# nRF24-MultiPro.net
KiCad netlist of a schematic drawn in EAGLE
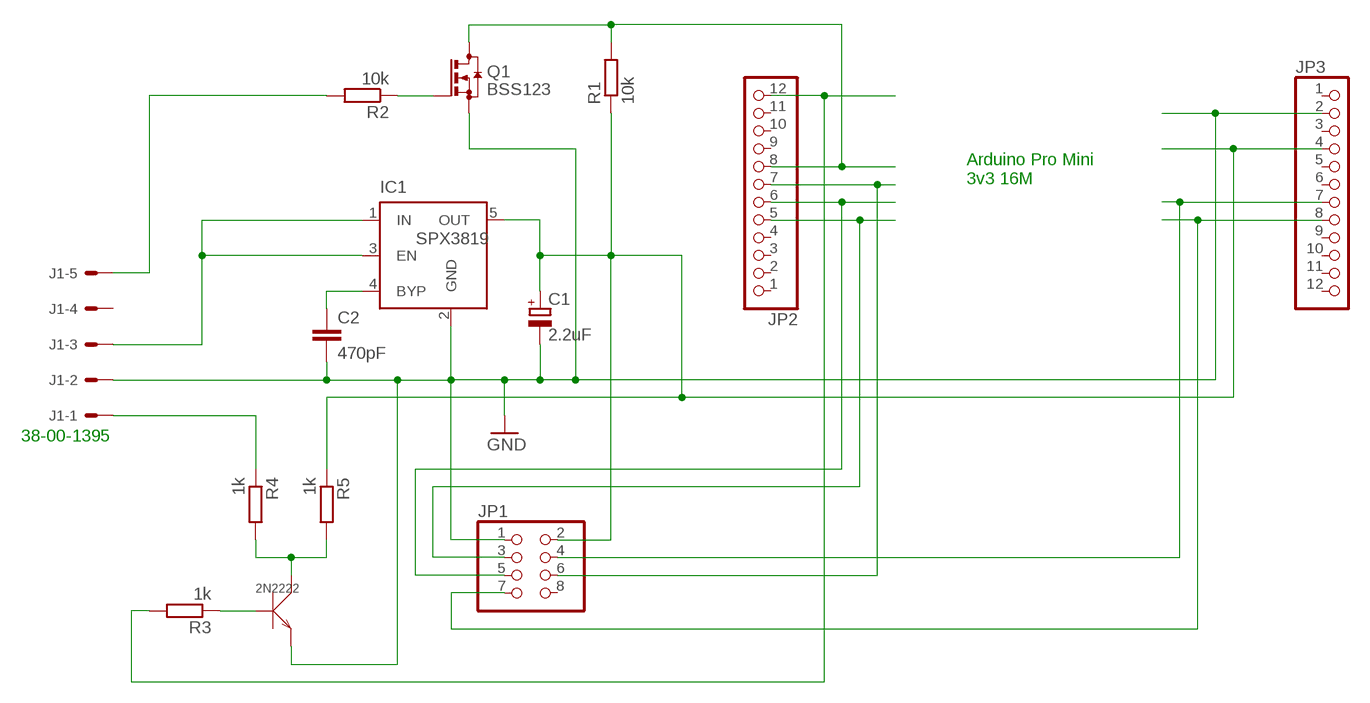
[diagram p0: schematic, sheet 1]

(export (version "E")
  (design (tool "Eeschema 10.0.6"))
  (components
    (comp (ref "2N2222")
      (value "TRANSISTOR-NPN")
      (footprint "eagle-import:SOT-23")
      (libsource (lib "eagle-import") (part "TRANSISTOR-NPN"))
    )
    (comp (ref "C1")
      (value "2.2uF")
      (footprint "eagle-import:A_3216-18W")
      (libsource (lib "eagle-import") (part "CPOL-EUA/3216-18W"))
    )
    (comp (ref "C2")
      (value "470pF")
      (footprint "eagle-import:C0805")
      (libsource (lib "eagle-import") (part "C-EUC0805"))
    )
    (comp (ref "IC1")
      (value "SPX3819")
      (footprint "eagle-import:SOT23-5")
      (libsource (lib "eagle-import") (part "MIC5219XX"))
    )
    (comp (ref "J1")
      (value "22-27-2051-05")
      (footprint "eagle-import:6410-05")
      (libsource (lib "eagle-import") (part "22-?-0527-2051"))
    )
    (comp (ref "JP1")
      (value "PINHD-2X4")
      (footprint "eagle-import:2X04")
      (libsource (lib "eagle-import") (part "PINHD-2X4"))
    )
    (comp (ref "JP2")
      (value "PINHD-1X12")
      (footprint "eagle-import:1X12")
      (libsource (lib "eagle-import") (part "PINHD-1X12"))
    )
    (comp (ref "JP3")
      (value "PINHD-1X12")
      (footprint "eagle-import:1X12")
      (libsource (lib "eagle-import") (part "PINHD-1X12"))
    )
    (comp (ref "Q1")
      (value "BSS123")
      (footprint "eagle-import:SOT23")
      (libsource (lib "eagle-import") (part "BSS123"))
    )
    (comp (ref "R1")
      (value "10k")
      (footprint "eagle-import:R0805")
      (libsource (lib "eagle-import") (part "R-EU_R0805"))
    )
    (comp (ref "R2")
      (value "10k")
      (footprint "eagle-import:R0805")
      (libsource (lib "eagle-import") (part "R-EU_R0805"))
    )
    (comp (ref "R3")
      (value "1k")
      (footprint "eagle-import:R0805")
      (libsource (lib "eagle-import") (part "R-EU_R0805"))
    )
    (comp (ref "R4")
      (value "1k")
      (footprint "eagle-import:R0805")
      (libsource (lib "eagle-import") (part "R-EU_R0805"))
    )
    (comp (ref "R5")
      (value "1k")
      (footprint "eagle-import:R0805")
      (libsource (lib "eagle-import") (part "R-EU_R0805"))
    )
  )
  (nets
    (net (code "1") (name "GND") (class "Default")
      (node (ref "2N2222") (pin "2") (pinfunction "E_2") (pintype "passive"))
      (node (ref "C1") (pin "-") (pinfunction "-_-") (pintype "passive"))
      (node (ref "C2") (pin "2") (pinfunction "2_2") (pintype "passive"))
      (node (ref "IC1") (pin "2") (pinfunction "GND_2") (pintype "power_in"))
      (node (ref "J1") (pin "2") (pinfunction "S_2") (pintype "passive"))
      (node (ref "JP1") (pin "1") (pinfunction "1_1") (pintype "passive"))
      (node (ref "JP3") (pin "2") (pinfunction "2_2") (pintype "passive"))
      (node (ref "Q1") (pin "2") (pinfunction "S_2") (pintype "passive"))
    )
    (net (code "2") (name "Net-(2N2222-B)") (class "Default")
      (node (ref "2N2222") (pin "1") (pinfunction "B_1") (pintype "passive"))
      (node (ref "R3") (pin "1") (pinfunction "1_1") (pintype "passive"))
    )
    (net (code "3") (name "Net-(2N2222-C)") (class "Default")
      (node (ref "2N2222") (pin "3") (pinfunction "C_3") (pintype "passive"))
      (node (ref "R4") (pin "2") (pinfunction "2_2") (pintype "passive"))
      (node (ref "R5") (pin "2") (pinfunction "2_2") (pintype "passive"))
    )
    (net (code "4") (name "Net-(IC1-BYP)") (class "Default")
      (node (ref "C2") (pin "1") (pinfunction "1_1") (pintype "passive"))
      (node (ref "IC1") (pin "4") (pinfunction "BYP_4") (pintype "passive"))
    )
    (net (code "5") (name "Net-(IC1-EN)") (class "Default")
      (node (ref "IC1") (pin "1") (pinfunction "IN_1") (pintype "input"))
      (node (ref "IC1") (pin "3") (pinfunction "EN_3") (pintype "input"))
      (node (ref "J1") (pin "3") (pinfunction "S_3") (pintype "passive"))
    )
    (net (code "6") (name "Net-(IC1-OUT)") (class "Default")
      (node (ref "C1") (pin "+") (pinfunction "+_+") (pintype "passive"))
      (node (ref "IC1") (pin "5") (pinfunction "OUT_5") (pintype "output"))
      (node (ref "JP1") (pin "2") (pinfunction "2_2") (pintype "passive"))
      (node (ref "JP3") (pin "4") (pinfunction "4_4") (pintype "passive"))
      (node (ref "R1") (pin "1") (pinfunction "1_1") (pintype "passive"))
      (node (ref "R5") (pin "1") (pinfunction "1_1") (pintype "passive"))
    )
    (net (code "7") (name "Net-(J1A-S)") (class "Default")
      (node (ref "J1") (pin "1") (pinfunction "S_1") (pintype "passive"))
      (node (ref "R4") (pin "1") (pinfunction "1_1") (pintype "passive"))
    )
    (net (code "8") (name "Net-(J1E-S)") (class "Default")
      (node (ref "J1") (pin "5") (pinfunction "S_5") (pintype "passive"))
      (node (ref "R2") (pin "2") (pinfunction "2_2") (pintype "passive"))
    )
    (net (code "9") (name "Net-(JP1-Pad3)") (class "Default")
      (node (ref "JP1") (pin "3") (pinfunction "3_3") (pintype "passive"))
      (node (ref "JP2") (pin "5") (pinfunction "5_5") (pintype "passive"))
    )
    (net (code "10") (name "Net-(JP1-Pad4)") (class "Default")
      (node (ref "JP1") (pin "4") (pinfunction "4_4") (pintype "passive"))
      (node (ref "JP3") (pin "7") (pinfunction "7_7") (pintype "passive"))
    )
    (net (code "11") (name "Net-(JP1-Pad5)") (class "Default")
      (node (ref "JP1") (pin "5") (pinfunction "5_5") (pintype "passive"))
      (node (ref "JP2") (pin "6") (pinfunction "6_6") (pintype "passive"))
    )
    (net (code "12") (name "Net-(JP1-Pad6)") (class "Default")
      (node (ref "JP1") (pin "6") (pinfunction "6_6") (pintype "passive"))
      (node (ref "JP2") (pin "7") (pinfunction "7_7") (pintype "passive"))
    )
    (net (code "13") (name "Net-(JP1-Pad7)") (class "Default")
      (node (ref "JP1") (pin "7") (pinfunction "7_7") (pintype "passive"))
      (node (ref "JP3") (pin "8") (pinfunction "8_8") (pintype "passive"))
    )
    (net (code "14") (name "Net-(JP2-Pad12)") (class "Default")
      (node (ref "JP2") (pin "12") (pinfunction "12_12") (pintype "passive"))
      (node (ref "R3") (pin "2") (pinfunction "2_2") (pintype "passive"))
    )
    (net (code "15") (name "Net-(Q1-D)") (class "Default")
      (node (ref "JP2") (pin "8") (pinfunction "8_8") (pintype "passive"))
      (node (ref "Q1") (pin "3") (pinfunction "D_3") (pintype "passive"))
      (node (ref "R1") (pin "2") (pinfunction "2_2") (pintype "passive"))
    )
    (net (code "16") (name "Net-(Q1-G)") (class "Default")
      (node (ref "Q1") (pin "1") (pinfunction "G_1") (pintype "passive"))
      (node (ref "R2") (pin "1") (pinfunction "1_1") (pintype "passive"))
    )
    (net (code "17") (name "unconnected-(J1D-S-Pad4)") (class "Default")
      (node (ref "J1") (pin "4") (pinfunction "S_4") (pintype "passive"))
    )
    (net (code "18") (name "unconnected-(JP1-Pad8)") (class "Default")
      (node (ref "JP1") (pin "8") (pinfunction "8_8") (pintype "passive"))
    )
    (net (code "19") (name "unconnected-(JP2-Pad1)") (class "Default")
      (node (ref "JP2") (pin "1") (pinfunction "1_1") (pintype "passive"))
    )
    (net (code "20") (name "unconnected-(JP2-Pad2)") (class "Default")
      (node (ref "JP2") (pin "2") (pinfunction "2_2") (pintype "passive"))
    )
    (net (code "21") (name "unconnected-(JP2-Pad3)") (class "Default")
      (node (ref "JP2") (pin "3") (pinfunction "3_3") (pintype "passive"))
    )
    (net (code "22") (name "unconnected-(JP2-Pad4)") (class "Default")
      (node (ref "JP2") (pin "4") (pinfunction "4_4") (pintype "passive"))
    )
    (net (code "23") (name "unconnected-(JP2-Pad9)") (class "Default")
      (node (ref "JP2") (pin "9") (pinfunction "9_9") (pintype "passive"))
    )
    (net (code "24") (name "unconnected-(JP2-Pad10)") (class "Default")
      (node (ref "JP2") (pin "10") (pinfunction "10_10") (pintype "passive"))
    )
    (net (code "25") (name "unconnected-(JP2-Pad11)") (class "Default")
      (node (ref "JP2") (pin "11") (pinfunction "11_11") (pintype "passive"))
    )
    (net (code "26") (name "unconnected-(JP3-Pad1)") (class "Default")
      (node (ref "JP3") (pin "1") (pinfunction "1_1") (pintype "passive"))
    )
    (net (code "27") (name "unconnected-(JP3-Pad3)") (class "Default")
      (node (ref "JP3") (pin "3") (pinfunction "3_3") (pintype "passive"))
    )
    (net (code "28") (name "unconnected-(JP3-Pad5)") (class "Default")
      (node (ref "JP3") (pin "5") (pinfunction "5_5") (pintype "passive"))
    )
    (net (code "29") (name "unconnected-(JP3-Pad6)") (class "Default")
      (node (ref "JP3") (pin "6") (pinfunction "6_6") (pintype "passive"))
    )
    (net (code "30") (name "unconnected-(JP3-Pad9)") (class "Default")
      (node (ref "JP3") (pin "9") (pinfunction "9_9") (pintype "passive"))
    )
    (net (code "31") (name "unconnected-(JP3-Pad10)") (class "Default")
      (node (ref "JP3") (pin "10") (pinfunction "10_10") (pintype "passive"))
    )
    (net (code "32") (name "unconnected-(JP3-Pad11)") (class "Default")
      (node (ref "JP3") (pin "11") (pinfunction "11_11") (pintype "passive"))
    )
    (net (code "33") (name "unconnected-(JP3-Pad12)") (class "Default")
      (node (ref "JP3") (pin "12") (pinfunction "12_12") (pintype "passive"))
    )
  )
)
